# alim.net
KiCad netlist of a schematic drawn in Altium Designer
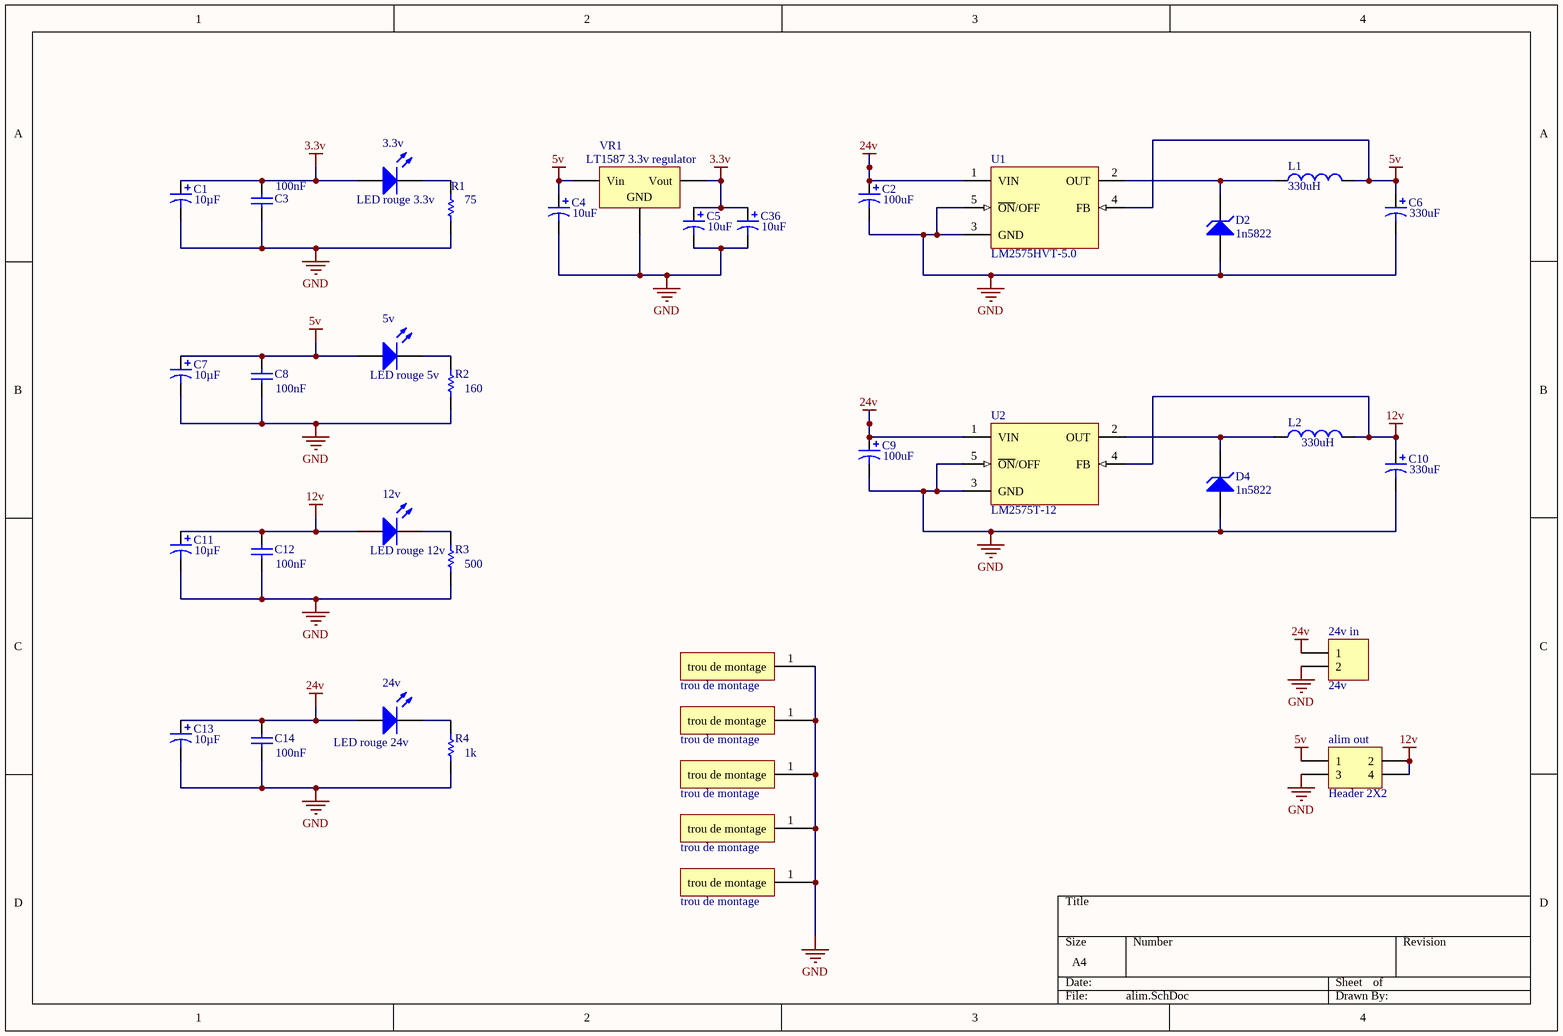
[diagram p0: alim.SchDoc]

(export (version "E")
  (design (tool "Eeschema 10.0.6"))
  (components
    (comp (ref "3.3v")
      (value "LED rouge 3.3v")
      (footprint "3.2X1.6X1.1")
      (description "Typical RED, GREEN, YELLOW, AMBER GaAs LED")
      (fields (field (name "PUBLISHER") "Altium Limited"))
      (libsource (lib "Miscellaneous Devices") (part "LED2"))
    )
    (comp (ref "5v")
      (value "LED rouge 5v")
      (footprint "3.2X1.6X1.1")
      (description "Typical RED, GREEN, YELLOW, AMBER GaAs LED")
      (fields (field (name "PUBLISHER") "Altium Limited"))
      (libsource (lib "Miscellaneous Devices") (part "LED2"))
    )
    (comp (ref "12v")
      (value "LED rouge 12v")
      (footprint "3.2X1.6X1.1")
      (description "Typical RED, GREEN, YELLOW, AMBER GaAs LED")
      (fields (field (name "PUBLISHER") "Altium Limited"))
      (libsource (lib "Miscellaneous Devices") (part "LED2"))
    )
    (comp (ref "24v")
      (value "LED rouge 24v")
      (footprint "3.2X1.6X1.1")
      (description "Typical RED, GREEN, YELLOW, AMBER GaAs LED")
      (fields (field (name "PUBLISHER") "Altium Limited"))
      (libsource (lib "Miscellaneous Devices") (part "LED2"))
    )
    (comp (ref "24v in")
      (value "24v")
      (footprint "power connector")
      (description "Header, 2-Pin")
      (fields (field (name "PUBLISHER") "Altium Limited"))
      (libsource (lib "Miscellaneous Connectors") (part "Header 2"))
    )
    (comp (ref "alim out")
      (value "Header 2X2")
      (footprint "5v et 12v connector")
      (description "Header, 2-Pin, Dual row")
      (fields (field (name "PUBLISHER") "Altium Limited"))
      (libsource (lib "Miscellaneous Connectors") (part "Header 2X2"))
    )
    (comp (ref "C1")
      (value "10µF")
      (footprint "CAPC3216M")
      (description "Polarized Capacitor (Surface Mount)")
      (fields (field (name "Comment") "Cap Pol3") (field (name "PUBLISHER") "Altium Limited"))
      (libsource (lib "Miscellaneous Devices") (part "Cap Pol3"))
    )
    (comp (ref "C2")
      (value "100uF")
      (footprint "CAPPR2-5x6.8")
      (description "Polarized Capacitor (Surface Mount)")
      (fields (field (name "Comment") "Cap Pol3") (field (name "PUBLISHER") "Altium Limited"))
      (libsource (lib "Miscellaneous Devices") (part "Cap Pol3"))
    )
    (comp (ref "C3")
      (value "100nF")
      (footprint "CAPC1608L")
      (description "Capacitor")
      (fields (field (name "Comment") "Cap") (field (name "PUBLISHER") "Altium Limited"))
      (libsource (lib "Miscellaneous Devices") (part "Cap"))
    )
    (comp (ref "C4")
      (value "10uF")
      (footprint "CAPC3216M")
      (description "Polarized Capacitor (Surface Mount)")
      (fields (field (name "Comment") "Cap Pol3") (field (name "PUBLISHER") "Altium Limited"))
      (libsource (lib "Miscellaneous Devices") (part "Cap Pol3"))
    )
    (comp (ref "C5")
      (value "10uF")
      (footprint "CAPC3216M")
      (description "Polarized Capacitor (Surface Mount)")
      (fields (field (name "Comment") "Cap Pol3") (field (name "PUBLISHER") "Altium Limited"))
      (libsource (lib "Miscellaneous Devices") (part "Cap Pol3"))
    )
    (comp (ref "C6")
      (value "330uF")
      (footprint "CAPPR5-10x12.5")
      (description "Polarized Capacitor (Surface Mount)")
      (fields (field (name "Comment") "Cap Pol3") (field (name "PUBLISHER") "Altium Limited"))
      (libsource (lib "Miscellaneous Devices") (part "Cap Pol3"))
    )
    (comp (ref "C7")
      (value "10µF")
      (footprint "CAPC3216M")
      (description "Polarized Capacitor (Surface Mount)")
      (fields (field (name "Comment") "Cap Pol3") (field (name "PUBLISHER") "Altium Limited"))
      (libsource (lib "Miscellaneous Devices") (part "Cap Pol3"))
    )
    (comp (ref "C8")
      (value "100nF")
      (footprint "CAPC1608L")
      (description "Capacitor")
      (fields (field (name "Comment") "Cap") (field (name "PUBLISHER") "Altium Limited"))
      (libsource (lib "Miscellaneous Devices") (part "Cap"))
    )
    (comp (ref "C9")
      (value "100uF")
      (footprint "CAPPR2-5x6.8")
      (description "Polarized Capacitor (Surface Mount)")
      (fields (field (name "Comment") "Cap Pol3") (field (name "PUBLISHER") "Altium Limited"))
      (libsource (lib "Miscellaneous Devices") (part "Cap Pol3"))
    )
    (comp (ref "C10")
      (value "330uF")
      (footprint "CAPPR5-10x12.5")
      (description "Polarized Capacitor (Surface Mount)")
      (fields (field (name "Comment") "Cap Pol3") (field (name "PUBLISHER") "Altium Limited"))
      (libsource (lib "Miscellaneous Devices") (part "Cap Pol3"))
    )
    (comp (ref "C11")
      (value "10µF")
      (footprint "CAPC3216M")
      (description "Polarized Capacitor (Surface Mount)")
      (fields (field (name "Comment") "Cap Pol3") (field (name "PUBLISHER") "Altium Limited"))
      (libsource (lib "Miscellaneous Devices") (part "Cap Pol3"))
    )
    (comp (ref "C12")
      (value "100nF")
      (footprint "CAPC1608L")
      (description "Capacitor")
      (fields (field (name "Comment") "Cap") (field (name "PUBLISHER") "Altium Limited"))
      (libsource (lib "Miscellaneous Devices") (part "Cap"))
    )
    (comp (ref "C13")
      (value "10µF")
      (footprint "CAPC3216M")
      (description "Polarized Capacitor (Surface Mount)")
      (fields (field (name "Comment") "Cap Pol3") (field (name "PUBLISHER") "Altium Limited"))
      (libsource (lib "Miscellaneous Devices") (part "Cap Pol3"))
    )
    (comp (ref "C14")
      (value "100nF")
      (footprint "CAPC1608L")
      (description "Capacitor")
      (fields (field (name "Comment") "Cap") (field (name "PUBLISHER") "Altium Limited"))
      (libsource (lib "Miscellaneous Devices") (part "Cap"))
    )
    (comp (ref "C36")
      (value "10uF")
      (footprint "CAPC3216M")
      (description "Polarized Capacitor (Surface Mount)")
      (fields (field (name "Comment") "Cap Pol3") (field (name "PUBLISHER") "Altium Limited"))
      (libsource (lib "Miscellaneous Devices") (part "Cap Pol3"))
    )
    (comp (ref "D2")
      (value "1n5822")
      (footprint "DIO18.84-9.6x5.6")
      (description "Zener Diode")
      (fields (field (name "PUBLISHER") "Altium Limited"))
      (libsource (lib "Miscellaneous Devices") (part "D Zener"))
    )
    (comp (ref "D4")
      (value "1n5822")
      (footprint "DIO18.84-9.6x5.6")
      (description "Zener Diode")
      (fields (field (name "PUBLISHER") "Altium Limited"))
      (libsource (lib "Miscellaneous Devices") (part "D Zener"))
    )
    (comp (ref "L1")
      (value "330uH")
      (footprint "CAPC4532L")
      (description "Inductor")
      (fields (field (name "PUBLISHER") "Altium Limited"))
      (libsource (lib "Miscellaneous Devices") (part "Inductor"))
    )
    (comp (ref "L2")
      (value "330uH")
      (footprint "CAPC4532L")
      (description "Inductor")
      (fields (field (name "PUBLISHER") "Altium Limited"))
      (libsource (lib "Miscellaneous Devices") (part "Inductor"))
    )
    (comp (ref "R1")
      (value "75")
      (footprint "RESC1608L")
      (description "Resistor")
      (fields (field (name "Comment") "Res1") (field (name "PUBLISHER") "Altium Limited"))
      (libsource (lib "Miscellaneous Devices") (part "Res1"))
    )
    (comp (ref "R2")
      (value "160")
      (footprint "RESC1608L")
      (description "Resistor")
      (fields (field (name "Comment") "Res1") (field (name "PUBLISHER") "Altium Limited"))
      (libsource (lib "Miscellaneous Devices") (part "Res1"))
    )
    (comp (ref "R3")
      (value "500")
      (footprint "RESC1608L")
      (description "Resistor")
      (fields (field (name "Comment") "Res1") (field (name "PUBLISHER") "Altium Limited"))
      (libsource (lib "Miscellaneous Devices") (part "Res1"))
    )
    (comp (ref "R4")
      (value "1k")
      (footprint "RESC1608L")
      (description "Resistor")
      (fields (field (name "Comment") "Res1") (field (name "PUBLISHER") "Altium Limited"))
      (libsource (lib "Miscellaneous Devices") (part "Res1"))
    )
    (comp (ref "T1")
      (value "trou de montage")
      (footprint "trou de montage")
      (libsource (lib "usbarm") (part "trou de montage"))
    )
    (comp (ref "T2")
      (value "trou de montage")
      (footprint "trou de montage")
      (libsource (lib "usbarm") (part "trou de montage"))
    )
    (comp (ref "T3")
      (value "trou de montage")
      (footprint "trou de montage")
      (libsource (lib "usbarm") (part "trou de montage"))
    )
    (comp (ref "T4")
      (value "trou de montage")
      (footprint "trou de montage")
      (libsource (lib "usbarm") (part "trou de montage"))
    )
    (comp (ref "T5")
      (value "trou de montage")
      (footprint "trou de montage")
      (libsource (lib "usbarm") (part "trou de montage"))
    )
    (comp (ref "U1")
      (value "LM2575HVT-5.0")
      (footprint "TO170P1524X460-6N")
      (description "SIMPLE SWITCHER 1A Step-Down Voltage Regulator")
      (fields
        (field (name "MANUFACTURER") "National Semiconductor")
        (field (name "DIGIKEYPARTNUMBER") "LM2575HVT-5.0-ND")
        (field (name "PUBLISHER") "Altium Limited")
      )
      (libsource (lib "NSC Switcher") (part "LM2575HVT-5.0"))
    )
    (comp (ref "U2")
      (value "LM2575T-12")
      (footprint "TO170P1524X460-6N")
      (description "SIMPLE SWITCHER 1A Step-Down Voltage Regulator")
      (fields
        (field (name "MANUFACTURER") "National Semiconductor")
        (field (name "DIGIKEYPARTNUMBER") "LM2575T-12-ND")
        (field (name "PUBLISHER") "Altium Limited")
      )
      (libsource (lib "NSC Switcher") (part "LM2575T-12"))
    )
    (comp (ref "VR1")
      (value "LT1587 3.3v regulator")
      (footprint "TO254P1435X457-4N")
      (description "Voltage Regulator")
      (fields (field (name "PUBLISHER") "Altium Limited"))
      (libsource (lib "Miscellaneous Devices") (part "Volt Reg"))
    )
  )
  (nets
    (net (code "1") (name "3.3v") (class "Default")
      (node (ref "3.3v") (pin "1") (pinfunction "A_1") (pintype "passive"))
      (node (ref "C1") (pin "1") (pinfunction "1_1") (pintype "passive"))
      (node (ref "C3") (pin "2") (pinfunction "2_2") (pintype "passive"))
      (node (ref "C36") (pin "1") (pinfunction "1_1") (pintype "passive"))
      (node (ref "C5") (pin "1") (pinfunction "1_1") (pintype "passive"))
      (node (ref "VR1") (pin "3") (pinfunction "Vout_3") (pintype "passive"))
    )
    (net (code "2") (name "5v") (class "Default")
      (node (ref "5v") (pin "1") (pinfunction "A_1") (pintype "passive"))
      (node (ref "C4") (pin "1") (pinfunction "1_1") (pintype "passive"))
      (node (ref "C6") (pin "1") (pinfunction "1_1") (pintype "passive"))
      (node (ref "C7") (pin "1") (pinfunction "1_1") (pintype "passive"))
      (node (ref "C8") (pin "2") (pinfunction "2_2") (pintype "passive"))
      (node (ref "L1") (pin "2") (pinfunction "2_2") (pintype "passive"))
      (node (ref "U1") (pin "4") (pinfunction "FB_4") (pintype "input"))
      (node (ref "VR1") (pin "1") (pinfunction "Vin_1") (pintype "passive"))
      (node (ref "alim out") (pin "1") (pinfunction "1_1") (pintype "passive"))
    )
    (net (code "3") (name "12v") (class "Default")
      (node (ref "12v") (pin "1") (pinfunction "A_1") (pintype "passive"))
      (node (ref "C10") (pin "1") (pinfunction "1_1") (pintype "passive"))
      (node (ref "C11") (pin "1") (pinfunction "1_1") (pintype "passive"))
      (node (ref "C12") (pin "2") (pinfunction "2_2") (pintype "passive"))
      (node (ref "L2") (pin "2") (pinfunction "2_2") (pintype "passive"))
      (node (ref "U2") (pin "4") (pinfunction "FB_4") (pintype "input"))
      (node (ref "alim out") (pin "2") (pinfunction "2_2") (pintype "passive"))
      (node (ref "alim out") (pin "4") (pinfunction "4_4") (pintype "passive"))
    )
    (net (code "4") (name "24v") (class "Default")
      (node (ref "24v") (pin "1") (pinfunction "A_1") (pintype "passive"))
      (node (ref "24v in") (pin "1") (pinfunction "1_1") (pintype "passive"))
      (node (ref "C13") (pin "1") (pinfunction "1_1") (pintype "passive"))
      (node (ref "C14") (pin "2") (pinfunction "2_2") (pintype "passive"))
      (node (ref "C2") (pin "1") (pinfunction "1_1") (pintype "passive"))
      (node (ref "C9") (pin "1") (pinfunction "1_1") (pintype "passive"))
      (node (ref "U1") (pin "1") (pinfunction "VIN_1") (pintype "power_in"))
      (node (ref "U2") (pin "1") (pinfunction "VIN_1") (pintype "power_in"))
    )
    (net (code "5") (name "GND") (class "Default")
      (node (ref "24v in") (pin "2") (pinfunction "2_2") (pintype "passive"))
      (node (ref "C1") (pin "2") (pinfunction "2_2") (pintype "passive"))
      (node (ref "C10") (pin "2") (pinfunction "2_2") (pintype "passive"))
      (node (ref "C11") (pin "2") (pinfunction "2_2") (pintype "passive"))
      (node (ref "C12") (pin "1") (pinfunction "1_1") (pintype "passive"))
      (node (ref "C13") (pin "2") (pinfunction "2_2") (pintype "passive"))
      (node (ref "C14") (pin "1") (pinfunction "1_1") (pintype "passive"))
      (node (ref "C2") (pin "2") (pinfunction "2_2") (pintype "passive"))
      (node (ref "C3") (pin "1") (pinfunction "1_1") (pintype "passive"))
      (node (ref "C36") (pin "2") (pinfunction "2_2") (pintype "passive"))
      (node (ref "C4") (pin "2") (pinfunction "2_2") (pintype "passive"))
      (node (ref "C5") (pin "2") (pinfunction "2_2") (pintype "passive"))
      (node (ref "C6") (pin "2") (pinfunction "2_2") (pintype "passive"))
      (node (ref "C7") (pin "2") (pinfunction "2_2") (pintype "passive"))
      (node (ref "C8") (pin "1") (pinfunction "1_1") (pintype "passive"))
      (node (ref "C9") (pin "2") (pinfunction "2_2") (pintype "passive"))
      (node (ref "D2") (pin "1") (pinfunction "A_1") (pintype "passive"))
      (node (ref "D4") (pin "1") (pinfunction "A_1") (pintype "passive"))
      (node (ref "R1") (pin "1") (pinfunction "1_1") (pintype "passive"))
      (node (ref "R2") (pin "1") (pinfunction "1_1") (pintype "passive"))
      (node (ref "R3") (pin "1") (pinfunction "1_1") (pintype "passive"))
      (node (ref "R4") (pin "1") (pinfunction "1_1") (pintype "passive"))
      (node (ref "T1") (pin "1") (pinfunction "trou_de_montage_1") (pintype "power_in"))
      (node (ref "T2") (pin "1") (pinfunction "trou_de_montage_1") (pintype "power_in"))
      (node (ref "T3") (pin "1") (pinfunction "trou_de_montage_1") (pintype "power_in"))
      (node (ref "T4") (pin "1") (pinfunction "trou_de_montage_1") (pintype "power_in"))
      (node (ref "T5") (pin "1") (pinfunction "trou_de_montage_1") (pintype "power_in"))
      (node (ref "U1") (pin "3") (pinfunction "GND_3") (pintype "power_in"))
      (node (ref "U1") (pin "5") (pinfunction "~{ON}/OFF_5") (pintype "input"))
      (node (ref "U2") (pin "3") (pinfunction "GND_3") (pintype "power_in"))
      (node (ref "U2") (pin "5") (pinfunction "~{ON}/OFF_5") (pintype "input"))
      (node (ref "VR1") (pin "2") (pinfunction "GND_2") (pintype "passive"))
      (node (ref "alim out") (pin "3") (pinfunction "3_3") (pintype "passive"))
    )
    (net (code "6") (name "Net-(3.3v-K)") (class "Default")
      (node (ref "3.3v") (pin "2") (pinfunction "K_2") (pintype "passive"))
      (node (ref "R1") (pin "2") (pinfunction "2_2") (pintype "passive"))
    )
    (net (code "7") (name "Net-(5v-K)") (class "Default")
      (node (ref "5v") (pin "2") (pinfunction "K_2") (pintype "passive"))
      (node (ref "R2") (pin "2") (pinfunction "2_2") (pintype "passive"))
    )
    (net (code "8") (name "Net-(12v-K)") (class "Default")
      (node (ref "12v") (pin "2") (pinfunction "K_2") (pintype "passive"))
      (node (ref "R3") (pin "2") (pinfunction "2_2") (pintype "passive"))
    )
    (net (code "9") (name "Net-(24v-K)") (class "Default")
      (node (ref "24v") (pin "2") (pinfunction "K_2") (pintype "passive"))
      (node (ref "R4") (pin "2") (pinfunction "2_2") (pintype "passive"))
    )
    (net (code "10") (name "Net-(D2-K)") (class "Default")
      (node (ref "D2") (pin "2") (pinfunction "K_2") (pintype "passive"))
      (node (ref "L1") (pin "1") (pinfunction "1_1") (pintype "passive"))
      (node (ref "U1") (pin "2") (pinfunction "OUT_2") (pintype "power_in"))
    )
    (net (code "11") (name "Net-(D4-K)") (class "Default")
      (node (ref "D4") (pin "2") (pinfunction "K_2") (pintype "passive"))
      (node (ref "L2") (pin "1") (pinfunction "1_1") (pintype "passive"))
      (node (ref "U2") (pin "2") (pinfunction "OUT_2") (pintype "power_in"))
    )
  )
)
